# BinClock.net
KiCad netlist of a schematic drawn in EAGLE
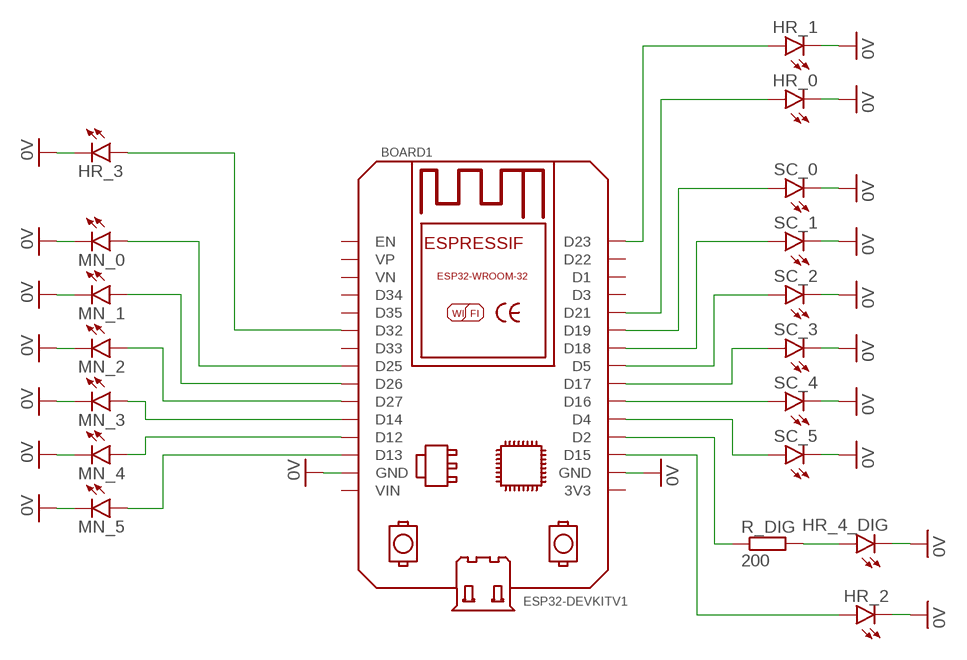
[diagram p0: schematic, sheet 1]

(export (version "E")
  (design (tool "Eeschema 10.0.6"))
  (components
    (comp (ref "BOARD1")
      (value "ESP32DEVKITV1")
      (footprint "eagle-import:ESP32-DEVKITV1")
      (libsource (lib "eagle-import") (part "ESP32DEVKITV1"))
    )
    (comp (ref "HR_0")
      (value "LEDSQR2X5")
      (footprint "eagle-import:LED2X5")
      (libsource (lib "eagle-import") (part "LEDSQR2X5"))
    )
    (comp (ref "HR_1")
      (value "LEDSQR2X5")
      (footprint "eagle-import:LED2X5")
      (libsource (lib "eagle-import") (part "LEDSQR2X5"))
    )
    (comp (ref "HR_2")
      (value "LEDSQR2X5")
      (footprint "eagle-import:LED2X5")
      (libsource (lib "eagle-import") (part "LEDSQR2X5"))
    )
    (comp (ref "HR_3")
      (value "LEDSQR2X5")
      (footprint "eagle-import:LED2X5")
      (libsource (lib "eagle-import") (part "LEDSQR2X5"))
    )
    (comp (ref "HR_4_DIG")
      (value "LEDSQR2X5")
      (footprint "eagle-import:LED2X5")
      (libsource (lib "eagle-import") (part "LEDSQR2X5"))
    )
    (comp (ref "MN_0")
      (value "LEDSQR2X5")
      (footprint "eagle-import:LED2X5")
      (libsource (lib "eagle-import") (part "LEDSQR2X5"))
    )
    (comp (ref "MN_1")
      (value "LEDSQR2X5")
      (footprint "eagle-import:LED2X5")
      (libsource (lib "eagle-import") (part "LEDSQR2X5"))
    )
    (comp (ref "MN_2")
      (value "LEDSQR2X5")
      (footprint "eagle-import:LED2X5")
      (libsource (lib "eagle-import") (part "LEDSQR2X5"))
    )
    (comp (ref "MN_3")
      (value "LEDSQR2X5")
      (footprint "eagle-import:LED2X5")
      (libsource (lib "eagle-import") (part "LEDSQR2X5"))
    )
    (comp (ref "MN_4")
      (value "LEDSQR2X5")
      (footprint "eagle-import:LED2X5")
      (libsource (lib "eagle-import") (part "LEDSQR2X5"))
    )
    (comp (ref "MN_5")
      (value "LEDSQR2X5")
      (footprint "eagle-import:LED2X5")
      (libsource (lib "eagle-import") (part "LEDSQR2X5"))
    )
    (comp (ref "R_DIG")
      (value "200")
      (footprint "eagle-import:0204_7")
      (libsource (lib "eagle-import") (part "R-EU_0204/7"))
    )
    (comp (ref "SC_0")
      (value "LEDSQR2X5")
      (footprint "eagle-import:LED2X5")
      (libsource (lib "eagle-import") (part "LEDSQR2X5"))
    )
    (comp (ref "SC_1")
      (value "LEDSQR2X5")
      (footprint "eagle-import:LED2X5")
      (libsource (lib "eagle-import") (part "LEDSQR2X5"))
    )
    (comp (ref "SC_2")
      (value "LEDSQR2X5")
      (footprint "eagle-import:LED2X5")
      (libsource (lib "eagle-import") (part "LEDSQR2X5"))
    )
    (comp (ref "SC_3")
      (value "LEDSQR2X5")
      (footprint "eagle-import:LED2X5")
      (libsource (lib "eagle-import") (part "LEDSQR2X5"))
    )
    (comp (ref "SC_4")
      (value "LEDSQR2X5")
      (footprint "eagle-import:LED2X5")
      (libsource (lib "eagle-import") (part "LEDSQR2X5"))
    )
    (comp (ref "SC_5")
      (value "LEDSQR2X5")
      (footprint "eagle-import:LED2X5")
      (libsource (lib "eagle-import") (part "LEDSQR2X5"))
    )
  )
  (nets
    (net (code "1") (name "0V") (class "Default")
      (node (ref "BOARD1") (pin "GND") (pinfunction "GND_GND") (pintype "bidirectional"))
      (node (ref "BOARD1") (pin "GND@1") (pinfunction "GND_GND@1") (pintype "bidirectional"))
      (node (ref "HR_0") (pin "K") (pinfunction "C_K") (pintype "passive"))
      (node (ref "HR_1") (pin "K") (pinfunction "C_K") (pintype "passive"))
      (node (ref "HR_2") (pin "K") (pinfunction "C_K") (pintype "passive"))
      (node (ref "HR_3") (pin "K") (pinfunction "C_K") (pintype "passive"))
      (node (ref "HR_4_DIG") (pin "K") (pinfunction "C_K") (pintype "passive"))
      (node (ref "MN_0") (pin "K") (pinfunction "C_K") (pintype "passive"))
      (node (ref "MN_1") (pin "K") (pinfunction "C_K") (pintype "passive"))
      (node (ref "MN_2") (pin "K") (pinfunction "C_K") (pintype "passive"))
      (node (ref "MN_3") (pin "K") (pinfunction "C_K") (pintype "passive"))
      (node (ref "MN_4") (pin "K") (pinfunction "C_K") (pintype "passive"))
      (node (ref "MN_5") (pin "K") (pinfunction "C_K") (pintype "passive"))
      (node (ref "SC_0") (pin "K") (pinfunction "C_K") (pintype "passive"))
      (node (ref "SC_1") (pin "K") (pinfunction "C_K") (pintype "passive"))
      (node (ref "SC_2") (pin "K") (pinfunction "C_K") (pintype "passive"))
      (node (ref "SC_3") (pin "K") (pinfunction "C_K") (pintype "passive"))
      (node (ref "SC_4") (pin "K") (pinfunction "C_K") (pintype "passive"))
      (node (ref "SC_5") (pin "K") (pinfunction "C_K") (pintype "passive"))
    )
    (net (code "2") (name "Net-(BOARD1-PadD2)") (class "Default")
      (node (ref "BOARD1") (pin "D2") (pinfunction "D2_D2") (pintype "bidirectional"))
      (node (ref "R_DIG") (pin "1") (pinfunction "1_1") (pintype "passive"))
    )
    (net (code "3") (name "Net-(BOARD1-PadD4)") (class "Default")
      (node (ref "BOARD1") (pin "D4") (pinfunction "D4_D4") (pintype "bidirectional"))
      (node (ref "SC_5") (pin "A") (pinfunction "A_A") (pintype "passive"))
    )
    (net (code "4") (name "Net-(BOARD1-PadD5)") (class "Default")
      (node (ref "BOARD1") (pin "D5") (pinfunction "D5_D5") (pintype "bidirectional"))
      (node (ref "SC_2") (pin "A") (pinfunction "A_A") (pintype "passive"))
    )
    (net (code "5") (name "Net-(BOARD1-PadD12)") (class "Default")
      (node (ref "BOARD1") (pin "D12") (pinfunction "D12_D12") (pintype "bidirectional"))
      (node (ref "MN_4") (pin "A") (pinfunction "A_A") (pintype "passive"))
    )
    (net (code "6") (name "Net-(BOARD1-PadD13)") (class "Default")
      (node (ref "BOARD1") (pin "D13") (pinfunction "D13_D13") (pintype "bidirectional"))
      (node (ref "MN_5") (pin "A") (pinfunction "A_A") (pintype "passive"))
    )
    (net (code "7") (name "Net-(BOARD1-PadD14)") (class "Default")
      (node (ref "BOARD1") (pin "D14") (pinfunction "D14_D14") (pintype "bidirectional"))
      (node (ref "MN_3") (pin "A") (pinfunction "A_A") (pintype "passive"))
    )
    (net (code "8") (name "Net-(BOARD1-PadD15)") (class "Default")
      (node (ref "BOARD1") (pin "D15") (pinfunction "D15_D15") (pintype "bidirectional"))
      (node (ref "HR_2") (pin "A") (pinfunction "A_A") (pintype "passive"))
    )
    (net (code "9") (name "Net-(BOARD1-PadD16)") (class "Default")
      (node (ref "BOARD1") (pin "D16") (pinfunction "D16_D16") (pintype "bidirectional"))
      (node (ref "SC_4") (pin "A") (pinfunction "A_A") (pintype "passive"))
    )
    (net (code "10") (name "Net-(BOARD1-PadD17)") (class "Default")
      (node (ref "BOARD1") (pin "D17") (pinfunction "D17_D17") (pintype "bidirectional"))
      (node (ref "SC_3") (pin "A") (pinfunction "A_A") (pintype "passive"))
    )
    (net (code "11") (name "Net-(BOARD1-PadD18)") (class "Default")
      (node (ref "BOARD1") (pin "D18") (pinfunction "D18_D18") (pintype "bidirectional"))
      (node (ref "SC_1") (pin "A") (pinfunction "A_A") (pintype "passive"))
    )
    (net (code "12") (name "Net-(BOARD1-PadD19)") (class "Default")
      (node (ref "BOARD1") (pin "D19") (pinfunction "D19_D19") (pintype "bidirectional"))
      (node (ref "SC_0") (pin "A") (pinfunction "A_A") (pintype "passive"))
    )
    (net (code "13") (name "Net-(BOARD1-PadD21)") (class "Default")
      (node (ref "BOARD1") (pin "D21") (pinfunction "D21_D21") (pintype "bidirectional"))
      (node (ref "HR_0") (pin "A") (pinfunction "A_A") (pintype "passive"))
    )
    (net (code "14") (name "Net-(BOARD1-PadD23)") (class "Default")
      (node (ref "BOARD1") (pin "D23") (pinfunction "D23_D23") (pintype "bidirectional"))
      (node (ref "HR_1") (pin "A") (pinfunction "A_A") (pintype "passive"))
    )
    (net (code "15") (name "Net-(BOARD1-PadD25)") (class "Default")
      (node (ref "BOARD1") (pin "D25") (pinfunction "D25_D25") (pintype "bidirectional"))
      (node (ref "MN_0") (pin "A") (pinfunction "A_A") (pintype "passive"))
    )
    (net (code "16") (name "Net-(BOARD1-PadD26)") (class "Default")
      (node (ref "BOARD1") (pin "D26") (pinfunction "D26_D26") (pintype "bidirectional"))
      (node (ref "MN_1") (pin "A") (pinfunction "A_A") (pintype "passive"))
    )
    (net (code "17") (name "Net-(BOARD1-PadD27)") (class "Default")
      (node (ref "BOARD1") (pin "D27") (pinfunction "D27_D27") (pintype "bidirectional"))
      (node (ref "MN_2") (pin "A") (pinfunction "A_A") (pintype "passive"))
    )
    (net (code "18") (name "Net-(BOARD1-PadD32)") (class "Default")
      (node (ref "BOARD1") (pin "D32") (pinfunction "D32_D32") (pintype "bidirectional"))
      (node (ref "HR_3") (pin "A") (pinfunction "A_A") (pintype "passive"))
    )
    (net (code "19") (name "Net-(HR_4_DIG-PadA)") (class "Default")
      (node (ref "HR_4_DIG") (pin "A") (pinfunction "A_A") (pintype "passive"))
      (node (ref "R_DIG") (pin "2") (pinfunction "2_2") (pintype "passive"))
    )
    (net (code "20") (name "unconnected-(BOARD1-Pad3V3)") (class "Default")
      (node (ref "BOARD1") (pin "3V3") (pinfunction "3V3_3V3") (pintype "bidirectional"))
    )
    (net (code "21") (name "unconnected-(BOARD1-PadD1)") (class "Default")
      (node (ref "BOARD1") (pin "D1") (pinfunction "D1_D1") (pintype "bidirectional"))
    )
    (net (code "22") (name "unconnected-(BOARD1-PadD3)") (class "Default")
      (node (ref "BOARD1") (pin "D3") (pinfunction "D3_D3") (pintype "bidirectional"))
    )
    (net (code "23") (name "unconnected-(BOARD1-PadD22)") (class "Default")
      (node (ref "BOARD1") (pin "D22") (pinfunction "D22_D22") (pintype "bidirectional"))
    )
    (net (code "24") (name "unconnected-(BOARD1-PadD33)") (class "Default")
      (node (ref "BOARD1") (pin "D33") (pinfunction "D33_D33") (pintype "bidirectional"))
    )
    (net (code "25") (name "unconnected-(BOARD1-PadD34)") (class "Default")
      (node (ref "BOARD1") (pin "D34") (pinfunction "D34_D34") (pintype "bidirectional"))
    )
    (net (code "26") (name "unconnected-(BOARD1-PadD35)") (class "Default")
      (node (ref "BOARD1") (pin "D35") (pinfunction "D35_D35") (pintype "bidirectional"))
    )
    (net (code "27") (name "unconnected-(BOARD1-PadEN)") (class "Default")
      (node (ref "BOARD1") (pin "EN") (pinfunction "EN_EN") (pintype "bidirectional"))
    )
    (net (code "28") (name "unconnected-(BOARD1-PadVIN)") (class "Default")
      (node (ref "BOARD1") (pin "VIN") (pinfunction "VIN_VIN") (pintype "bidirectional"))
    )
    (net (code "29") (name "unconnected-(BOARD1-PadVN)") (class "Default")
      (node (ref "BOARD1") (pin "VN") (pinfunction "VN_VN") (pintype "bidirectional"))
    )
    (net (code "30") (name "unconnected-(BOARD1-PadVP)") (class "Default")
      (node (ref "BOARD1") (pin "VP") (pinfunction "VP_VP") (pintype "bidirectional"))
    )
  )
)
